# BV100011_MCU144.net
KiCad netlist of a schematic drawn in Altium Designer
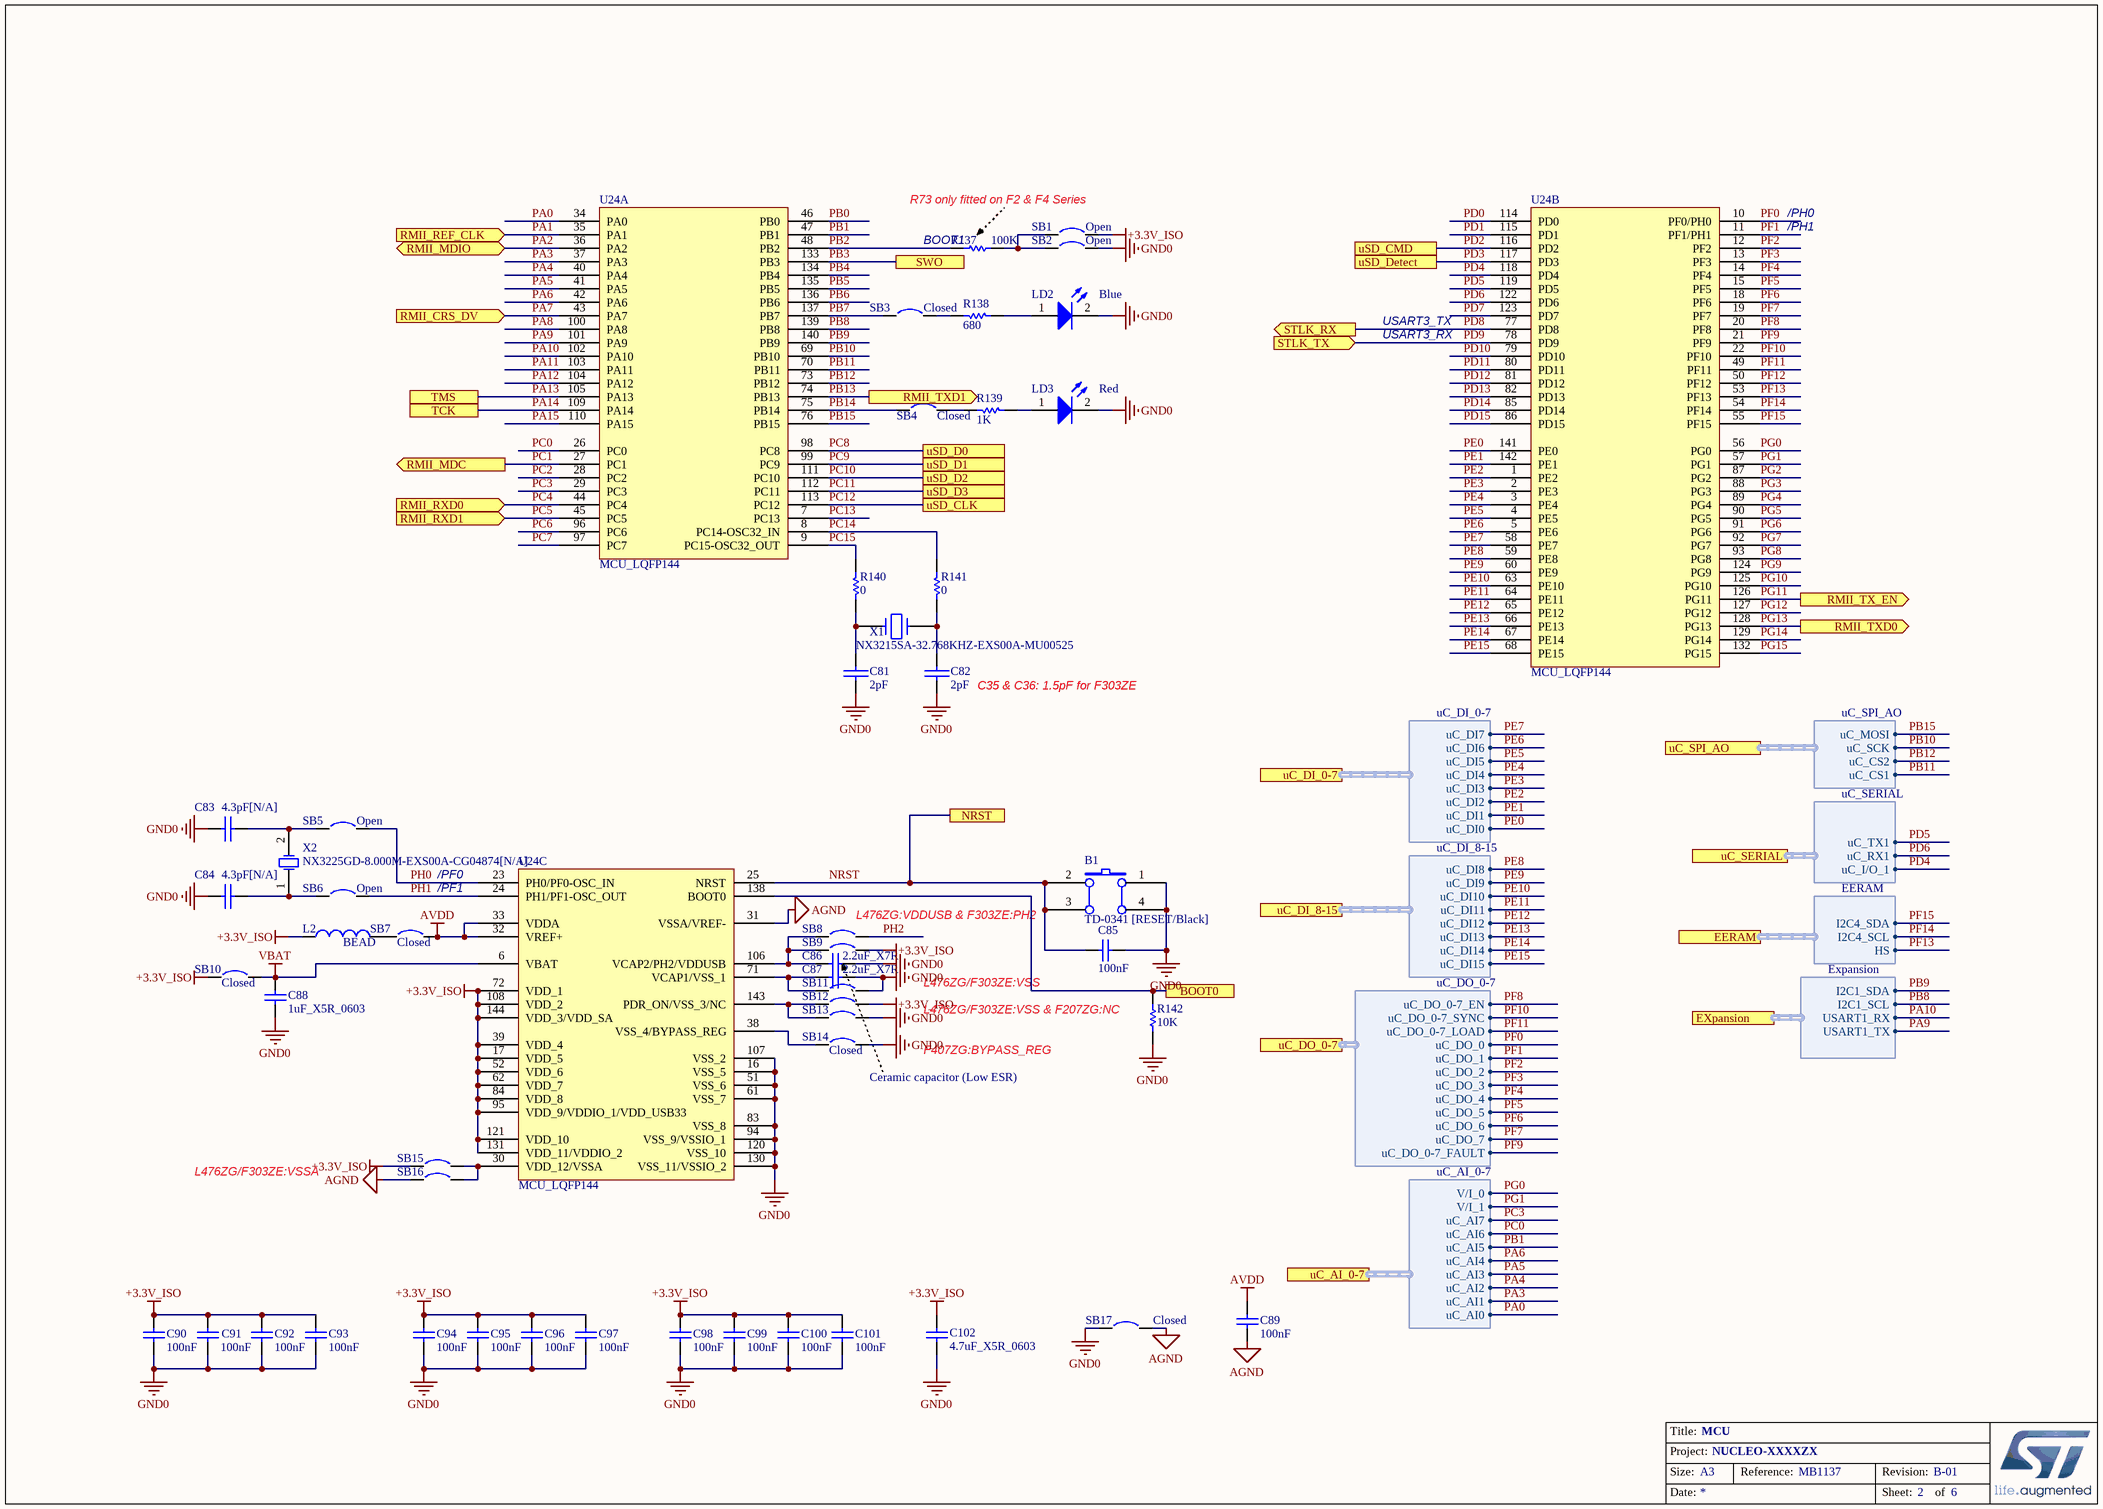
[diagram p0: BV100011_MCU144.SchDoc]

(export (version "E")
  (design (tool "Eeschema 10.0.6"))
  (components
    (comp (ref "B1")
      (value "TD-0341 [RESET/Black]")
      (footprint "PB-6X6mm-Black")
      (description "SE PUSHBUTTON")
      (libsource (lib "Documents") (part "SW PUSHBUTTON"))
    )
    (comp (ref "C81")
      (value "2pF")
      (footprint "0603C")
      (description "Capacitor")
      (libsource (lib "*") (part "CAP"))
    )
    (comp (ref "C82")
      (value "2pF")
      (footprint "0603C")
      (description "Capacitor")
      (libsource (lib "*") (part "CAP"))
    )
    (comp (ref "C83")
      (value "4.3pF[N/A]")
      (footprint "0603C")
      (description "Capacitor")
      (libsource (lib "") (part "CAP_1"))
    )
    (comp (ref "C84")
      (value "4.3pF[N/A]")
      (footprint "0603C")
      (description "Capacitor")
      (libsource (lib "") (part "CAP_1"))
    )
    (comp (ref "C85")
      (value "100nF")
      (footprint "0603C")
      (description "Capacitor")
      (fields (field (name "PUBLISHER") "Altium Limited"))
      (libsource (lib "Miscellaneous Devices") (part "CAP"))
    )
    (comp (ref "C86")
      (value "2.2uF_X7R")
      (footprint "TAN-A")
      (description "Capacitor,2.2uF,16V, X7R,10%,0805,YAGEO")
      (libsource (lib "MCD_TOOLS") (part "Cap_2.2uF_X7R_10%_0805"))
    )
    (comp (ref "C87")
      (value "2.2uF_X7R")
      (footprint "TAN-A")
      (description "Capacitor,2.2uF,16V, X7R,10%,0805,YAGEO")
      (libsource (lib "MCD_TOOLS") (part "Cap_2.2uF_X7R_10%_0805"))
    )
    (comp (ref "C88")
      (value "1uF_X5R_0603")
      (footprint "0603C")
      (description "0603  X5R 1µF")
      (fields (field (name "TOLERANCE") "10%"))
      (libsource (lib "MB963_1") (part "CAP SMD 0603  X5R 1µF 25V 10%"))
    )
    (comp (ref "C89")
      (value "100nF")
      (footprint "0603C")
      (description "Capacitor")
      (fields (field (name "PUBLISHER") "Altium Limited"))
      (libsource (lib "Miscellaneous Devices") (part "Cap"))
    )
    (comp (ref "C90")
      (value "100nF")
      (footprint "0603C")
      (description "Capacitor")
      (fields (field (name "PUBLISHER") "Altium Limited"))
      (libsource (lib "Miscellaneous Devices") (part "Cap"))
    )
    (comp (ref "C91")
      (value "100nF")
      (footprint "0603C")
      (description "Capacitor")
      (fields (field (name "PUBLISHER") "Altium Limited"))
      (libsource (lib "Miscellaneous Devices") (part "Cap"))
    )
    (comp (ref "C92")
      (value "100nF")
      (footprint "0603C")
      (description "Capacitor")
      (fields (field (name "PUBLISHER") "Altium Limited"))
      (libsource (lib "Miscellaneous Devices") (part "Cap"))
    )
    (comp (ref "C93")
      (value "100nF")
      (footprint "0603C")
      (description "Capacitor")
      (fields (field (name "PUBLISHER") "Altium Limited"))
      (libsource (lib "Miscellaneous Devices") (part "Cap"))
    )
    (comp (ref "C94")
      (value "100nF")
      (footprint "0603C")
      (description "Capacitor")
      (fields (field (name "PUBLISHER") "Altium Limited"))
      (libsource (lib "Miscellaneous Devices") (part "Cap"))
    )
    (comp (ref "C95")
      (value "100nF")
      (footprint "0603C")
      (description "Capacitor")
      (fields (field (name "PUBLISHER") "Altium Limited"))
      (libsource (lib "Miscellaneous Devices") (part "Cap"))
    )
    (comp (ref "C96")
      (value "100nF")
      (footprint "0603C")
      (description "Capacitor")
      (fields (field (name "PUBLISHER") "Altium Limited"))
      (libsource (lib "Miscellaneous Devices") (part "Cap"))
    )
    (comp (ref "C97")
      (value "100nF")
      (footprint "0603C")
      (description "Capacitor")
      (fields (field (name "PUBLISHER") "Altium Limited"))
      (libsource (lib "Miscellaneous Devices") (part "Cap"))
    )
    (comp (ref "C98")
      (value "100nF")
      (footprint "0603C")
      (description "Capacitor")
      (fields (field (name "PUBLISHER") "Altium Limited"))
      (libsource (lib "Miscellaneous Devices") (part "Cap"))
    )
    (comp (ref "C99")
      (value "100nF")
      (footprint "0603C")
      (description "Capacitor")
      (fields (field (name "PUBLISHER") "Altium Limited"))
      (libsource (lib "Miscellaneous Devices") (part "Cap"))
    )
    (comp (ref "C100")
      (value "100nF")
      (footprint "0603C")
      (description "Capacitor")
      (fields (field (name "PUBLISHER") "Altium Limited"))
      (libsource (lib "Miscellaneous Devices") (part "Cap"))
    )
    (comp (ref "C101")
      (value "100nF")
      (footprint "0603C")
      (description "Capacitor")
      (fields (field (name "PUBLISHER") "Altium Limited"))
      (libsource (lib "Miscellaneous Devices") (part "Cap"))
    )
    (comp (ref "C102")
      (value "4.7uF_X5R_0603")
      (footprint "0603C")
      (description "0603  X5R 4.7uF")
      (fields (field (name "TOLERANCE") "10%"))
      (libsource (lib "MB963_1") (part "CAP SMD 0603  X5R 1µF 25V 10%"))
    )
    (comp (ref "L2")
      (value "BEAD")
      (footprint "0603L")
      (description "Inductor")
      (fields (field (name "PUBLISHER") "Altium Limited"))
      (libsource (lib "Miscellaneous Devices") (part "Inductor"))
    )
    (comp (ref "LD2")
      (value "Blue")
      (footprint "0603D-B")
      (description "Typical RED, GREEN, YELLOW, AMBER GaAs LED")
      (fields (field (name "PUBLISHER") "Altium Limited"))
      (libsource (lib "Miscellaneous Devices") (part "LED2"))
    )
    (comp (ref "LD3")
      (value "Red")
      (footprint "0603D-R")
      (description "Typical RED, GREEN, YELLOW, AMBER GaAs LED")
      (fields (field (name "PUBLISHER") "Altium Limited"))
      (libsource (lib "Miscellaneous Devices") (part "LED2"))
    )
    (comp (ref "R137")
      (value "100K")
      (footprint "0603R")
      (description "Resistor")
      (fields (field (name "PUBLISHER") "Altium Limited"))
      (libsource (lib "Miscellaneous Devices") (part "res1"))
    )
    (comp (ref "R138")
      (value "680")
      (footprint "0603R")
      (description "Resistor")
      (fields (field (name "PUBLISHER") "Altium Limited"))
      (libsource (lib "Miscellaneous Devices") (part "Res1"))
    )
    (comp (ref "R139")
      (value "1K")
      (footprint "0603R")
      (description "Resistor")
      (fields (field (name "PUBLISHER") "Altium Limited"))
      (libsource (lib "Miscellaneous Devices") (part "Res1"))
    )
    (comp (ref "R140")
      (value "0")
      (footprint "0603R")
      (description "Resistor")
      (fields (field (name "PUBLISHER") "Altium Limited"))
      (libsource (lib "Miscellaneous Devices") (part "Res1"))
    )
    (comp (ref "R141")
      (value "0")
      (footprint "0603R")
      (description "Resistor")
      (fields (field (name "PUBLISHER") "Altium Limited"))
      (libsource (lib "Miscellaneous Devices") (part "Res1"))
    )
    (comp (ref "R142")
      (value "10K")
      (footprint "0603R")
      (description "Resistor")
      (fields (field (name "PUBLISHER") "Altium Limited"))
      (libsource (lib "Miscellaneous Devices") (part "res1"))
    )
    (comp (ref "SB1")
      (value "Open")
      (footprint "SB_0603")
      (description "Circuit Breaker")
      (fields (field (name "PUBLISHER") "Altium Limited"))
      (libsource (lib "MB1167") (part "Circuit Breaker"))
    )
    (comp (ref "SB2")
      (value "Open")
      (footprint "SB_0603")
      (description "Circuit Breaker")
      (fields (field (name "PUBLISHER") "Altium Limited"))
      (libsource (lib "MB1167") (part "Circuit Breaker"))
    )
    (comp (ref "SB3")
      (value "Closed")
      (footprint "SB_0603")
      (description "Circuit Breaker")
      (fields (field (name "PUBLISHER") "Altium Limited"))
      (libsource (lib "MB1167") (part "Circuit Breaker_close"))
    )
    (comp (ref "SB4")
      (value "Closed")
      (footprint "SB_0603")
      (description "Circuit Breaker")
      (fields (field (name "PUBLISHER") "Altium Limited"))
      (libsource (lib "MB1167") (part "Circuit Breaker_close"))
    )
    (comp (ref "SB5")
      (value "Open")
      (footprint "SB_0603")
      (description "Circuit Breaker")
      (fields (field (name "PUBLISHER") "Altium Limited"))
      (libsource (lib "MB1167") (part "Circuit Breaker"))
    )
    (comp (ref "SB6")
      (value "Open")
      (footprint "SB_0603")
      (description "Circuit Breaker")
      (fields (field (name "PUBLISHER") "Altium Limited"))
      (libsource (lib "MB1167") (part "Circuit Breaker"))
    )
    (comp (ref "SB7")
      (value "Closed")
      (footprint "SB_0603")
      (description "Circuit Breaker")
      (fields (field (name "PUBLISHER") "Altium Limited"))
      (libsource (lib "MB1167") (part "Circuit Breaker_close"))
    )
    (comp (ref "SB8")
      (value "Circuit Breaker")
      (footprint "SB_0603")
      (fields (field (name "PUBLISHER") "Altium Limited"))
      (libsource (lib "MCD_TOOLS") (part "Circuit Breaker"))
    )
    (comp (ref "SB9")
      (value "Circuit Breaker")
      (footprint "SB_0603")
      (fields (field (name "PUBLISHER") "Altium Limited"))
      (libsource (lib "MCD_TOOLS") (part "Circuit Breaker"))
    )
    (comp (ref "SB10")
      (value "Closed")
      (footprint "SB_0603")
      (description "Circuit Breaker")
      (fields (field (name "PUBLISHER") "Altium Limited"))
      (libsource (lib "MB1167") (part "Circuit Breaker_close"))
    )
    (comp (ref "SB11")
      (value "Circuit Breaker")
      (footprint "SB_0603")
      (fields (field (name "PUBLISHER") "Altium Limited"))
      (libsource (lib "MCD_TOOLS") (part "Circuit Breaker"))
    )
    (comp (ref "SB12")
      (value "Circuit Breaker")
      (footprint "SB_0603")
      (fields (field (name "PUBLISHER") "Altium Limited"))
      (libsource (lib "MCD_TOOLS") (part "Circuit Breaker"))
    )
    (comp (ref "SB13")
      (value "Circuit Breaker")
      (footprint "SB_0603")
      (fields (field (name "PUBLISHER") "Altium Limited"))
      (libsource (lib "MCD_TOOLS") (part "Circuit Breaker"))
    )
    (comp (ref "SB14")
      (value "Closed")
      (footprint "SB_0603")
      (description "Circuit Breaker")
      (fields (field (name "PUBLISHER") "Altium Limited"))
      (libsource (lib "MB1167") (part "Circuit Breaker_close"))
    )
    (comp (ref "SB15")
      (value "Circuit Breaker")
      (footprint "SB_0603")
      (fields (field (name "PUBLISHER") "Altium Limited"))
      (libsource (lib "MCD_TOOLS") (part "Circuit Breaker"))
    )
    (comp (ref "SB16")
      (value "Circuit Breaker")
      (footprint "SB_0603")
      (fields (field (name "PUBLISHER") "Altium Limited"))
      (libsource (lib "MCD_TOOLS") (part "Circuit Breaker"))
    )
    (comp (ref "SB17")
      (value "Closed")
      (footprint "SB_0603")
      (description "Circuit Breaker")
      (fields (field (name "PUBLISHER") "Altium Limited"))
      (libsource (lib "MB1167") (part "Circuit Breaker_close"))
    )
    (comp (ref "U24")
      (value "MCU_LQFP144")
      (footprint "LQFP144_0R5_SKT")
      (libsource (lib "MB1137") (part "MCU_LQFP144"))
    )
    (comp (ref "X1")
      (value "NX3215SA-32.768KHZ-EXS00A-MU00525")
      (footprint "XTAL_2SM_3R2X1R5")
      (description "Crystal")
      (libsource (lib "MB1167") (part "CRYSTAL_32K"))
    )
    (comp (ref "X2")
      (value "NX3225GD-8.000M-EXS00A-CG04874[N/A]")
      (footprint "OSC_2SM_3R2x2R5")
      (description "Crystal Oscillator")
      (fields (field (name "PUBLISHER") "Altium Limited"))
      (libsource (lib "MB963_1") (part "XTAL"))
    )
  )
  (nets
    (net (code "9") (name "+3.3V_ISO") (class "Default")
      (node (ref "C100") (pin "1") (pinfunction "1_1") (pintype "passive"))
      (node (ref "C101") (pin "1") (pinfunction "1_1") (pintype "passive"))
      (node (ref "C102") (pin "1") (pinfunction "1_1") (pintype "passive"))
      (node (ref "C90") (pin "1") (pinfunction "1_1") (pintype "passive"))
      (node (ref "C91") (pin "1") (pinfunction "1_1") (pintype "passive"))
      (node (ref "C92") (pin "1") (pinfunction "1_1") (pintype "passive"))
      (node (ref "C93") (pin "1") (pinfunction "1_1") (pintype "passive"))
      (node (ref "C94") (pin "1") (pinfunction "1_1") (pintype "passive"))
      (node (ref "C95") (pin "1") (pinfunction "1_1") (pintype "passive"))
      (node (ref "C96") (pin "1") (pinfunction "1_1") (pintype "passive"))
      (node (ref "C97") (pin "1") (pinfunction "1_1") (pintype "passive"))
      (node (ref "C98") (pin "1") (pinfunction "1_1") (pintype "passive"))
      (node (ref "C99") (pin "1") (pinfunction "1_1") (pintype "passive"))
      (node (ref "L2") (pin "1") (pinfunction "1_1") (pintype "passive"))
      (node (ref "SB1") (pin "2") (pinfunction "2_2") (pintype "passive"))
      (node (ref "SB10") (pin "1") (pinfunction "1_1") (pintype "passive"))
      (node (ref "SB12") (pin "2") (pinfunction "2_2") (pintype "passive"))
      (node (ref "SB15") (pin "1") (pinfunction "1_1") (pintype "passive"))
      (node (ref "SB9") (pin "2") (pinfunction "2_2") (pintype "passive"))
      (node (ref "U24") (pin "108") (pinfunction "VDD_2_108") (pintype "passive"))
      (node (ref "U24") (pin "121") (pinfunction "VDD_10_121") (pintype "passive"))
      (node (ref "U24") (pin "131") (pinfunction "VDD_11/VDDIO_2_131") (pintype "passive"))
      (node (ref "U24") (pin "144") (pinfunction "VDD_3/VDD_SA_144") (pintype "passive"))
      (node (ref "U24") (pin "17") (pinfunction "VDD_5_17") (pintype "passive"))
      (node (ref "U24") (pin "39") (pinfunction "VDD_4_39") (pintype "passive"))
      (node (ref "U24") (pin "52") (pinfunction "VDD_6_52") (pintype "passive"))
      (node (ref "U24") (pin "62") (pinfunction "VDD_7_62") (pintype "passive"))
      (node (ref "U24") (pin "72") (pinfunction "VDD_1_72") (pintype "passive"))
      (node (ref "U24") (pin "84") (pinfunction "VDD_8_84") (pintype "passive"))
      (node (ref "U24") (pin "95") (pinfunction "VDD_9/VDDIO_1/VDD_USB33_95") (pintype "passive"))
    )
    (net (code "10") (name "/BOOT0") (class "Default")
      (node (ref "R142") (pin "1") (pinfunction "1_1") (pintype "passive"))
      (node (ref "U24") (pin "138") (pinfunction "BOOT0_138") (pintype "passive"))
    )
    (net (code "11") (name "/NRST") (class "Default")
      (node (ref "B1") (pin "2") (pinfunction "B0_2") (pintype "passive"))
      (node (ref "B1") (pin "3") (pinfunction "B1_3") (pintype "passive"))
      (node (ref "C85") (pin "2") (pinfunction "2_2") (pintype "passive"))
      (node (ref "U24") (pin "25") (pinfunction "NRST_25") (pintype "passive"))
    )
    (net (code "12") (name "/PA0") (class "Default")
      (node (ref "U24") (pin "34") (pinfunction "PA0_34") (pintype "passive"))
    )
    (net (code "13") (name "/PA1") (class "Default")
      (node (ref "U24") (pin "35") (pinfunction "PA1_35") (pintype "passive"))
    )
    (net (code "14") (name "/PA2") (class "Default")
      (node (ref "U24") (pin "36") (pinfunction "PA2_36") (pintype "passive"))
    )
    (net (code "15") (name "/PA3") (class "Default")
      (node (ref "U24") (pin "37") (pinfunction "PA3_37") (pintype "passive"))
    )
    (net (code "16") (name "/PA4") (class "Default")
      (node (ref "U24") (pin "40") (pinfunction "PA4_40") (pintype "passive"))
    )
    (net (code "17") (name "/PA5") (class "Default")
      (node (ref "U24") (pin "41") (pinfunction "PA5_41") (pintype "passive"))
    )
    (net (code "18") (name "/PA6") (class "Default")
      (node (ref "U24") (pin "42") (pinfunction "PA6_42") (pintype "passive"))
    )
    (net (code "19") (name "/PA7") (class "Default")
      (node (ref "U24") (pin "43") (pinfunction "PA7_43") (pintype "passive"))
    )
    (net (code "20") (name "/PA8") (class "Default")
      (node (ref "U24") (pin "100") (pinfunction "PA8_100") (pintype "passive"))
    )
    (net (code "21") (name "/PA9") (class "Default")
      (node (ref "U24") (pin "101") (pinfunction "PA9_101") (pintype "passive"))
    )
    (net (code "22") (name "/PA10") (class "Default")
      (node (ref "U24") (pin "102") (pinfunction "PA10_102") (pintype "passive"))
    )
    (net (code "23") (name "/PA11") (class "Default")
      (node (ref "U24") (pin "103") (pinfunction "PA11_103") (pintype "passive"))
    )
    (net (code "24") (name "/PA12") (class "Default")
      (node (ref "U24") (pin "104") (pinfunction "PA12_104") (pintype "passive"))
    )
    (net (code "25") (name "/PA13") (class "Default")
      (node (ref "U24") (pin "105") (pinfunction "PA13_105") (pintype "passive"))
    )
    (net (code "26") (name "/PA14") (class "Default")
      (node (ref "U24") (pin "109") (pinfunction "PA14_109") (pintype "passive"))
    )
    (net (code "27") (name "/PA15") (class "Default")
      (node (ref "U24") (pin "110") (pinfunction "PA15_110") (pintype "passive"))
    )
    (net (code "28") (name "/PB0") (class "Default")
      (node (ref "U24") (pin "46") (pinfunction "PB0_46") (pintype "passive"))
    )
    (net (code "29") (name "/PB1") (class "Default")
      (node (ref "U24") (pin "47") (pinfunction "PB1_47") (pintype "passive"))
    )
    (net (code "30") (name "/PB2") (class "Default")
      (node (ref "R137") (pin "1") (pinfunction "1_1") (pintype "passive"))
      (node (ref "U24") (pin "48") (pinfunction "PB2_48") (pintype "passive"))
    )
    (net (code "31") (name "/PB3") (class "Default")
      (node (ref "U24") (pin "133") (pinfunction "PB3_133") (pintype "passive"))
    )
    (net (code "32") (name "/PB4") (class "Default")
      (node (ref "U24") (pin "134") (pinfunction "PB4_134") (pintype "passive"))
    )
    (net (code "33") (name "/PB5") (class "Default")
      (node (ref "U24") (pin "135") (pinfunction "PB5_135") (pintype "passive"))
    )
    (net (code "34") (name "/PB6") (class "Default")
      (node (ref "U24") (pin "136") (pinfunction "PB6_136") (pintype "passive"))
    )
    (net (code "35") (name "/PB7") (class "Default")
      (node (ref "SB3") (pin "1") (pinfunction "1_1") (pintype "passive"))
      (node (ref "U24") (pin "137") (pinfunction "PB7_137") (pintype "passive"))
    )
    (net (code "36") (name "/PB8") (class "Default")
      (node (ref "U24") (pin "139") (pinfunction "PB8_139") (pintype "passive"))
    )
    (net (code "37") (name "/PB9") (class "Default")
      (node (ref "U24") (pin "140") (pinfunction "PB9_140") (pintype "passive"))
    )
    (net (code "38") (name "/PB10") (class "Default")
      (node (ref "U24") (pin "69") (pinfunction "PB10_69") (pintype "passive"))
    )
    (net (code "39") (name "/PB11") (class "Default")
      (node (ref "U24") (pin "70") (pinfunction "PB11_70") (pintype "passive"))
    )
    (net (code "40") (name "/PB12") (class "Default")
      (node (ref "U24") (pin "73") (pinfunction "PB12_73") (pintype "passive"))
    )
    (net (code "41") (name "/PB13") (class "Default")
      (node (ref "U24") (pin "74") (pinfunction "PB13_74") (pintype "passive"))
    )
    (net (code "42") (name "/PB14") (class "Default")
      (node (ref "SB4") (pin "1") (pinfunction "1_1") (pintype "passive"))
      (node (ref "U24") (pin "75") (pinfunction "PB14_75") (pintype "passive"))
    )
    (net (code "43") (name "/PB15") (class "Default")
      (node (ref "U24") (pin "76") (pinfunction "PB15_76") (pintype "passive"))
    )
    (net (code "44") (name "/PC0") (class "Default")
      (node (ref "U24") (pin "26") (pinfunction "PC0_26") (pintype "passive"))
    )
    (net (code "45") (name "/PC1") (class "Default")
      (node (ref "U24") (pin "27") (pinfunction "PC1_27") (pintype "passive"))
    )
    (net (code "46") (name "/PC2") (class "Default")
      (node (ref "U24") (pin "28") (pinfunction "PC2_28") (pintype "passive"))
    )
    (net (code "47") (name "/PC3") (class "Default")
      (node (ref "U24") (pin "29") (pinfunction "PC3_29") (pintype "passive"))
    )
    (net (code "48") (name "/PC4") (class "Default")
      (node (ref "U24") (pin "44") (pinfunction "PC4_44") (pintype "passive"))
    )
    (net (code "49") (name "/PC5") (class "Default")
      (node (ref "U24") (pin "45") (pinfunction "PC5_45") (pintype "passive"))
    )
    (net (code "50") (name "/PC6") (class "Default")
      (node (ref "U24") (pin "96") (pinfunction "PC6_96") (pintype "passive"))
    )
    (net (code "51") (name "/PC7") (class "Default")
      (node (ref "U24") (pin "97") (pinfunction "PC7_97") (pintype "passive"))
    )
    (net (code "52") (name "/PC8") (class "Default")
      (node (ref "U24") (pin "98") (pinfunction "PC8_98") (pintype "passive"))
    )
    (net (code "53") (name "/PC9") (class "Default")
      (node (ref "U24") (pin "99") (pinfunction "PC9_99") (pintype "passive"))
    )
    (net (code "54") (name "/PC10") (class "Default")
      (node (ref "U24") (pin "111") (pinfunction "PC10_111") (pintype "passive"))
    )
    (net (code "55") (name "/PC11") (class "Default")
      (node (ref "U24") (pin "112") (pinfunction "PC11_112") (pintype "passive"))
    )
    (net (code "56") (name "/PC12") (class "Default")
      (node (ref "U24") (pin "113") (pinfunction "PC12_113") (pintype "passive"))
    )
    (net (code "57") (name "/PC13") (class "Default")
      (node (ref "U24") (pin "7") (pinfunction "PC13_7") (pintype "passive"))
    )
    (net (code "58") (name "/PC14") (class "Default")
      (node (ref "R141") (pin "2") (pinfunction "2_2") (pintype "passive"))
      (node (ref "U24") (pin "8") (pinfunction "PC14-OSC32_IN_8") (pintype "passive"))
    )
    (net (code "59") (name "/PC15") (class "Default")
      (node (ref "R140") (pin "2") (pinfunction "2_2") (pintype "passive"))
      (node (ref "U24") (pin "9") (pinfunction "PC15-OSC32_OUT_9") (pintype "passive"))
    )
    (net (code "60") (name "/PD0") (class "Default")
      (node (ref "U24") (pin "114") (pinfunction "PD0_114") (pintype "passive"))
    )
    (net (code "61") (name "/PD1") (class "Default")
      (node (ref "U24") (pin "115") (pinfunction "PD1_115") (pintype "passive"))
    )
    (net (code "62") (name "/PD2") (class "Default")
      (node (ref "U24") (pin "116") (pinfunction "PD2_116") (pintype "passive"))
    )
    (net (code "63") (name "/PD3") (class "Default")
      (node (ref "U24") (pin "117") (pinfunction "PD3_117") (pintype "passive"))
    )
    (net (code "64") (name "/PD4") (class "Default")
      (node (ref "U24") (pin "118") (pinfunction "PD4_118") (pintype "passive"))
    )
    (net (code "65") (name "/PD5") (class "Default")
      (node (ref "U24") (pin "119") (pinfunction "PD5_119") (pintype "passive"))
    )
    (net (code "66") (name "/PD6") (class "Default")
      (node (ref "U24") (pin "122") (pinfunction "PD6_122") (pintype "passive"))
    )
    (net (code "67") (name "/PD7") (class "Default")
      (node (ref "U24") (pin "123") (pinfunction "PD7_123") (pintype "passive"))
    )
    (net (code "68") (name "/PD8") (class "Default")
      (node (ref "U24") (pin "77") (pinfunction "PD8_77") (pintype "passive"))
    )
    (net (code "69") (name "/PD9") (class "Default")
      (node (ref "U24") (pin "78") (pinfunction "PD9_78") (pintype "passive"))
    )
    (net (code "70") (name "/PD10") (class "Default")
      (node (ref "U24") (pin "79") (pinfunction "PD10_79") (pintype "passive"))
    )
    (net (code "71") (name "/PD11") (class "Default")
      (node (ref "U24") (pin "80") (pinfunction "PD11_80") (pintype "passive"))
    )
    (net (code "72") (name "/PD12") (class "Default")
      (node (ref "U24") (pin "81") (pinfunction "PD12_81") (pintype "passive"))
    )
    (net (code "73") (name "/PD13") (class "Default")
      (node (ref "U24") (pin "82") (pinfunction "PD13_82") (pintype "passive"))
    )
    (net (code "74") (name "/PD14") (class "Default")
      (node (ref "U24") (pin "85") (pinfunction "PD14_85") (pintype "passive"))
    )
    (net (code "75") (name "/PD15") (class "Default")
      (node (ref "U24") (pin "86") (pinfunction "PD15_86") (pintype "passive"))
    )
    (net (code "76") (name "/PE0") (class "Default")
      (node (ref "U24") (pin "141") (pinfunction "PE0_141") (pintype "passive"))
    )
    (net (code "77") (name "/PE1") (class "Default")
      (node (ref "U24") (pin "142") (pinfunction "PE1_142") (pintype "passive"))
    )
    (net (code "78") (name "/PE2") (class "Default")
      (node (ref "U24") (pin "1") (pinfunction "PE2_1") (pintype "passive"))
    )
    (net (code "79") (name "/PE3") (class "Default")
      (node (ref "U24") (pin "2") (pinfunction "PE3_2") (pintype "passive"))
    )
    (net (code "80") (name "/PE4") (class "Default")
      (node (ref "U24") (pin "3") (pinfunction "PE4_3") (pintype "passive"))
    )
    (net (code "81") (name "/PE5") (class "Default")
      (node (ref "U24") (pin "4") (pinfunction "PE5_4") (pintype "passive"))
    )
    (net (code "82") (name "/PE6") (class "Default")
      (node (ref "U24") (pin "5") (pinfunction "PE6_5") (pintype "passive"))
    )
    (net (code "83") (name "/PE7") (class "Default")
      (node (ref "U24") (pin "58") (pinfunction "PE7_58") (pintype "passive"))
    )
    (net (code "84") (name "/PE8") (class "Default")
      (node (ref "U24") (pin "59") (pinfunction "PE8_59") (pintype "passive"))
    )
    (net (code "85") (name "/PE9") (class "Default")
      (node (ref "U24") (pin "60") (pinfunction "PE9_60") (pintype "passive"))
    )
    (net (code "86") (name "/PE10") (class "Default")
      (node (ref "U24") (pin "63") (pinfunction "PE10_63") (pintype "passive"))
    )
    (net (code "87") (name "/PE11") (class "Default")
      (node (ref "U24") (pin "64") (pinfunction "PE11_64") (pintype "passive"))
    )
    (net (code "88") (name "/PE12") (class "Default")
      (node (ref "U24") (pin "65") (pinfunction "PE12_65") (pintype "passive"))
    )
    (net (code "89") (name "/PE13") (class "Default")
      (node (ref "U24") (pin "66") (pinfunction "PE13_66") (pintype "passive"))
    )
    (net (code "90") (name "/PE14") (class "Default")
      (node (ref "U24") (pin "67") (pinfunction "PE14_67") (pintype "passive"))
    )
    (net (code "91") (name "/PE15") (class "Default")
      (node (ref "U24") (pin "68") (pinfunction "PE15_68") (pintype "passive"))
    )
    (net (code "92") (name "/PF0") (class "Default")
      (node (ref "U24") (pin "10") (pinfunction "PF0/PH0_10") (pintype "passive"))
    )
    (net (code "93") (name "/PF1") (class "Default")
      (node (ref "U24") (pin "11") (pinfunction "PF1/PH1_11") (pintype "passive"))
    )
    (net (code "94") (name "/PF2") (class "Default")
      (node (ref "U24") (pin "12") (pinfunction "PF2_12") (pintype "passive"))
    )
    (net (code "95") (name "/PF3") (class "Default")
      (node (ref "U24") (pin "13") (pinfunction "PF3_13") (pintype "passive"))
    )
    (net (code "96") (name "/PF4") (class "Default")
      (node (ref "U24") (pin "14") (pinfunction "PF4_14") (pintype "passive"))
    )
    (net (code "97") (name "/PF5") (class "Default")
      (node (ref "U24") (pin "15") (pinfunction "PF5_15") (pintype "passive"))
    )
    (net (code "98") (name "/PF6") (class "Default")
      (node (ref "U24") (pin "18") (pinfunction "PF6_18") (pintype "passive"))
    )
    (net (code "99") (name "/PF7") (class "Default")
      (node (ref "U24") (pin "19") (pinfunction "PF7_19") (pintype "passive"))
    )
    (net (code "100") (name "/PF8") (class "Default")
      (node (ref "U24") (pin "20") (pinfunction "PF8_20") (pintype "passive"))
    )
    (net (code "101") (name "/PF9") (class "Default")
      (node (ref "U24") (pin "21") (pinfunction "PF9_21") (pintype "passive"))
    )
    (net (code "102") (name "/PF10") (class "Default")
      (node (ref "U24") (pin "22") (pinfunction "PF10_22") (pintype "passive"))
    )
    (net (code "103") (name "/PF11") (class "Default")
      (node (ref "U24") (pin "49") (pinfunction "PF11_49") (pintype "passive"))
    )
    (net (code "104") (name "/PF12") (class "Default")
      (node (ref "U24") (pin "50") (pinfunction "PF12_50") (pintype "passive"))
    )
    (net (code "105") (name "/PF13") (class "Default")
      (node (ref "U24") (pin "53") (pinfunction "PF13_53") (pintype "passive"))
    )
    (net (code "106") (name "/PF14") (class "Default")
      (node (ref "U24") (pin "54") (pinfunction "PF14_54") (pintype "passive"))
    )
    (net (code "107") (name "/PF15") (class "Default")
      (node (ref "U24") (pin "55") (pinfunction "PF15_55") (pintype "passive"))
    )
    (net (code "108") (name "/PG0") (class "Default")
      (node (ref "U24") (pin "56") (pinfunction "PG0_56") (pintype "passive"))
    )
    (net (code "109") (name "/PG1") (class "Default")
      (node (ref "U24") (pin "57") (pinfunction "PG1_57") (pintype "passive"))
    )
    (net (code "110") (name "/PG2") (class "Default")
      (node (ref "U24") (pin "87") (pinfunction "PG2_87") (pintype "passive"))
    )
    (net (code "111") (name "/PG3") (class "Default")
      (node (ref "U24") (pin "88") (pinfunction "PG3_88") (pintype "passive"))
    )
    (net (code "112") (name "/PG4") (class "Default")
      (node (ref "U24") (pin "89") (pinfunction "PG4_89") (pintype "passive"))
    )
    (net (code "113") (name "/PG5") (class "Default")
      (node (ref "U24") (pin "90") (pinfunction "PG5_90") (pintype "passive"))
    )
    (net (code "114") (name "/PG6") (class "Default")
      (node (ref "U24") (pin "91") (pinfunction "PG6_91") (pintype "passive"))
    )
    (net (code "115") (name "/PG7") (class "Default")
      (node (ref "U24") (pin "92") (pinfunction "PG7_92") (pintype "passive"))
    )
    (net (code "116") (name "/PG8") (class "Default")
      (node (ref "U24") (pin "93") (pinfunction "PG8_93") (pintype "passive"))
    )
    (net (code "117") (name "/PG9") (class "Default")
      (node (ref "U24") (pin "124") (pinfunction "PG9_124") (pintype "passive"))
    )
    (net (code "118") (name "/PG10") (class "Default")
      (node (ref "U24") (pin "125") (pinfunction "PG10_125") (pintype "passive"))
    )
    (net (code "119") (name "/PG11") (class "Default")
      (node (ref "U24") (pin "126") (pinfunction "PG11_126") (pintype "passive"))
    )
    (net (code "120") (name "/PG12") (class "Default")
      (node (ref "U24") (pin "127") (pinfunction "PG12_127") (pintype "passive"))
    )
    (net (code "121") (name "/PG13") (class "Default")
      (node (ref "U24") (pin "128") (pinfunction "PG13_128") (pintype "passive"))
    )
    (net (code "122") (name "/PG14") (class "Default")
      (node (ref "U24") (pin "129") (pinfunction "PG14_129") (pintype "passive"))
    )
    (net (code "123") (name "/PG15") (class "Default")
      (node (ref "U24") (pin "132") (pinfunction "PG15_132") (pintype "passive"))
    )
    (net (code "124") (name "/PH0") (class "Default")
      (node (ref "SB5") (pin "2") (pinfunction "2_2") (pintype "passive"))
      (node (ref "U24") (pin "23") (pinfunction "PH0/PF0-OSC_IN_23") (pintype "passive"))
    )
    (net (code "125") (name "/PH1") (class "Default")
      (node (ref "SB6") (pin "2") (pinfunction "2_2") (pintype "passive"))
      (node (ref "U24") (pin "24") (pinfunction "PH1/PF1-OSC_OUT_24") (pintype "passive"))
    )
    (net (code "126") (name "/PH2") (class "Default")
      (node (ref "SB8") (pin "2") (pinfunction "2_2") (pintype "passive"))
    )
    (net (code "135") (name "AGND") (class "Default")
      (node (ref "C89") (pin "2") (pinfunction "2_2") (pintype "passive"))
      (node (ref "SB16") (pin "1") (pinfunction "1_1") (pintype "passive"))
      (node (ref "SB17") (pin "2") (pinfunction "2_2") (pintype "passive"))
      (node (ref "U24") (pin "31") (pinfunction "VSSA/VREF-_31") (pintype "passive"))
    )
    (net (code "136") (name "AVDD") (class "Default")
      (node (ref "C89") (pin "1") (pinfunction "1_1") (pintype "passive"))
      (node (ref "SB7") (pin "2") (pinfunction "2_2") (pintype "passive"))
      (node (ref "U24") (pin "32") (pinfunction "VREF+_32") (pintype "passive"))
      (node (ref "U24") (pin "33") (pinfunction "VDDA_33") (pintype "passive"))
    )
    (net (code "137") (name "GND0") (class "Default")
      (node (ref "B1") (pin "1") (pinfunction "A0_1") (pintype "passive"))
      (node (ref "B1") (pin "4") (pinfunction "A1_4") (pintype "passive"))
      (node (ref "C100") (pin "2") (pinfunction "2_2") (pintype "passive"))
      (node (ref "C101") (pin "2") (pinfunction "2_2") (pintype "passive"))
      (node (ref "C102") (pin "2") (pinfunction "2_2") (pintype "passive"))
      (node (ref "C81") (pin "2") (pinfunction "2_2") (pintype "passive"))
      (node (ref "C82") (pin "2") (pinfunction "2_2") (pintype "passive"))
      (node (ref "C83") (pin "2") (pinfunction "2_2") (pintype "passive"))
      (node (ref "C84") (pin "2") (pinfunction "2_2") (pintype "passive"))
      (node (ref "C85") (pin "1") (pinfunction "1_1") (pintype "passive"))
      (node (ref "C86") (pin "2") (pinfunction "2_2") (pintype "passive"))
      (node (ref "C87") (pin "2") (pinfunction "2_2") (pintype "passive"))
      (node (ref "C88") (pin "2") (pinfunction "2_2") (pintype "passive"))
      (node (ref "C90") (pin "2") (pinfunction "2_2") (pintype "passive"))
      (node (ref "C91") (pin "2") (pinfunction "2_2") (pintype "passive"))
      (node (ref "C92") (pin "2") (pinfunction "2_2") (pintype "passive"))
      (node (ref "C93") (pin "2") (pinfunction "2_2") (pintype "passive"))
      (node (ref "C94") (pin "2") (pinfunction "2_2") (pintype "passive"))
      (node (ref "C95") (pin "2") (pinfunction "2_2") (pintype "passive"))
      (node (ref "C96") (pin "2") (pinfunction "2_2") (pintype "passive"))
      (node (ref "C97") (pin "2") (pinfunction "2_2") (pintype "passive"))
      (node (ref "C98") (pin "2") (pinfunction "2_2") (pintype "passive"))
      (node (ref "C99") (pin "2") (pinfunction "2_2") (pintype "passive"))
      (node (ref "LD2") (pin "2") (pinfunction "K_2") (pintype "passive"))
      (node (ref "LD3") (pin "2") (pinfunction "K_2") (pintype "passive"))
      (node (ref "R142") (pin "2") (pinfunction "2_2") (pintype "passive"))
      (node (ref "SB11") (pin "2") (pinfunction "2_2") (pintype "passive"))
      (node (ref "SB13") (pin "2") (pinfunction "2_2") (pintype "passive"))
      (node (ref "SB14") (pin "2") (pinfunction "2_2") (pintype "passive"))
      (node (ref "SB17") (pin "1") (pinfunction "1_1") (pintype "passive"))
      (node (ref "SB2") (pin "2") (pinfunction "2_2") (pintype "passive"))
      (node (ref "U24") (pin "107") (pinfunction "VSS_2_107") (pintype "passive"))
      (node (ref "U24") (pin "120") (pinfunction "VSS_10_120") (pintype "passive"))
      (node (ref "U24") (pin "130") (pinfunction "VSS_11/VSSIO_2_130") (pintype "passive"))
      (node (ref "U24") (pin "16") (pinfunction "VSS_5_16") (pintype "passive"))
      (node (ref "U24") (pin "51") (pinfunction "VSS_6_51") (pintype "passive"))
      (node (ref "U24") (pin "61") (pinfunction "VSS_7_61") (pintype "passive"))
      (node (ref "U24") (pin "83") (pinfunction "VSS_8_83") (pintype "passive"))
      (node (ref "U24") (pin "94") (pinfunction "VSS_9/VSSIO_1_94") (pintype "passive"))
    )
    (net (code "138") (name "Net-(C81-Pad1)") (class "Default")
      (node (ref "C81") (pin "1") (pinfunction "1_1") (pintype "passive"))
      (node (ref "R140") (pin "1") (pinfunction "1_1") (pintype "passive"))
      (node (ref "X1") (pin "1") (pinfunction "1_1") (pintype "passive"))
    )
    (net (code "139") (name "Net-(C82-Pad1)") (class "Default")
      (node (ref "C82") (pin "1") (pinfunction "1_1") (pintype "passive"))
      (node (ref "R141") (pin "1") (pinfunction "1_1") (pintype "passive"))
      (node (ref "X1") (pin "2") (pinfunction "2_2") (pintype "passive"))
    )
    (net (code "140") (name "Net-(L2-Pad2)") (class "Default")
      (node (ref "L2") (pin "2") (pinfunction "2_2") (pintype "passive"))
      (node (ref "SB7") (pin "1") (pinfunction "1_1") (pintype "passive"))
    )
    (net (code "141") (name "Net-(LD2-A)") (class "Default")
      (node (ref "LD2") (pin "1") (pinfunction "A_1") (pintype "passive"))
      (node (ref "R138") (pin "2") (pinfunction "2_2") (pintype "passive"))
    )
    (net (code "142") (name "Net-(LD3-A)") (class "Default")
      (node (ref "LD3") (pin "1") (pinfunction "A_1") (pintype "passive"))
      (node (ref "R139") (pin "2") (pinfunction "2_2") (pintype "passive"))
    )
    (net (code "143") (name "Net-(R137-Pad2)") (class "Default")
      (node (ref "R137") (pin "2") (pinfunction "2_2") (pintype "passive"))
      (node (ref "SB1") (pin "1") (pinfunction "1_1") (pintype "passive"))
      (node (ref "SB2") (pin "1") (pinfunction "1_1") (pintype "passive"))
    )
    (net (code "144") (name "Net-(R138-Pad1)") (class "Default")
      (node (ref "R138") (pin "1") (pinfunction "1_1") (pintype "passive"))
      (node (ref "SB3") (pin "2") (pinfunction "2_2") (pintype "passive"))
    )
    (net (code "145") (name "Net-(R139-Pad1)") (class "Default")
      (node (ref "R139") (pin "1") (pinfunction "1_1") (pintype "passive"))
      (node (ref "SB4") (pin "2") (pinfunction "2_2") (pintype "passive"))
    )
    (net (code "146") (name "Net-(U24C-PDR_ON{slash}VSS_3{slash}NC)") (class "Default")
      (node (ref "SB12") (pin "1") (pinfunction "1_1") (pintype "passive"))
      (node (ref "SB13") (pin "1") (pinfunction "1_1") (pintype "passive"))
      (node (ref "U24") (pin "143") (pinfunction "PDR_ON/VSS_3/NC_143") (pintype "passive"))
    )
    (net (code "147") (name "Net-(U24C-VCAP1{slash}VSS_1)") (class "Default")
      (node (ref "C87") (pin "1") (pinfunction "1_1") (pintype "passive"))
      (node (ref "SB11") (pin "1") (pinfunction "1_1") (pintype "passive"))
      (node (ref "U24") (pin "71") (pinfunction "VCAP1/VSS_1_71") (pintype "passive"))
    )
    (net (code "148") (name "Net-(U24C-VCAP2{slash}PH2{slash}VDDUSB)") (class "Default")
      (node (ref "C86") (pin "1") (pinfunction "1_1") (pintype "passive"))
      (node (ref "SB8") (pin "1") (pinfunction "1_1") (pintype "passive"))
      (node (ref "SB9") (pin "1") (pinfunction "1_1") (pintype "passive"))
      (node (ref "U24") (pin "106") (pinfunction "VCAP2/PH2/VDDUSB_106") (pintype "passive"))
    )
    (net (code "149") (name "Net-(U24C-VDD_12{slash}VSSA)") (class "Default")
      (node (ref "SB15") (pin "2") (pinfunction "2_2") (pintype "passive"))
      (node (ref "SB16") (pin "2") (pinfunction "2_2") (pintype "passive"))
      (node (ref "U24") (pin "30") (pinfunction "VDD_12/VSSA_30") (pintype "passive"))
    )
    (net (code "150") (name "Net-(U24C-VSS_4{slash}BYPASS_REG)") (class "Default")
      (node (ref "SB14") (pin "1") (pinfunction "1_1") (pintype "passive"))
      (node (ref "U24") (pin "38") (pinfunction "VSS_4/BYPASS_REG_38") (pintype "passive"))
    )
    (net (code "151") (name "Net-(X2-OSC1)") (class "Default")
      (node (ref "C84") (pin "1") (pinfunction "1_1") (pintype "passive"))
      (node (ref "SB6") (pin "1") (pinfunction "1_1") (pintype "passive"))
      (node (ref "X2") (pin "1") (pinfunction "OSC1_1") (pintype "passive"))
    )
    (net (code "152") (name "Net-(X2-OSC2)") (class "Default")
      (node (ref "C83") (pin "1") (pinfunction "1_1") (pintype "passive"))
      (node (ref "SB5") (pin "1") (pinfunction "1_1") (pintype "passive"))
      (node (ref "X2") (pin "2") (pinfunction "OSC2_2") (pintype "passive"))
    )
    (net (code "153") (name "VBAT") (class "Default")
      (node (ref "C88") (pin "1") (pinfunction "1_1") (pintype "passive"))
      (node (ref "SB10") (pin "2") (pinfunction "2_2") (pintype "passive"))
      (node (ref "U24") (pin "6") (pinfunction "VBAT_6") (pintype "passive"))
    )
  )
)
